# Triac.net
KiCad netlist of a schematic drawn in EAGLE
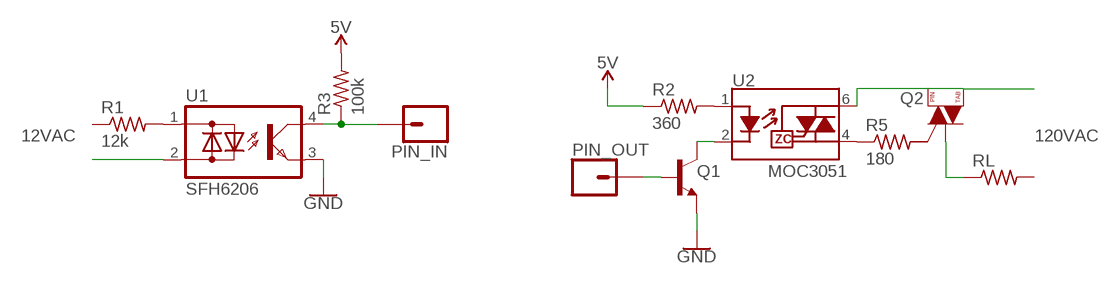
[diagram p0: schematic, sheet 1]

(export (version "E")
  (design (tool "Eeschema 10.0.6"))
  (components
    (comp (ref "PIN_IN")
      (value "CONN_01")
      (footprint "eagle-import:1X01")
      (libsource (lib "eagle-import") (part "CONN_01"))
    )
    (comp (ref "PIN_OUT")
      (value "CONN_01")
      (footprint "eagle-import:1X01")
      (libsource (lib "eagle-import") (part "CONN_01"))
    )
    (comp (ref "Q1")
      (value "TRANS_NPN-MMBTA42")
      (footprint "eagle-import:SOT23-3")
      (libsource (lib "eagle-import") (part "TRANS_NPN-MMBTA42"))
    )
    (comp (ref "Q2")
      (value "BT137-600E")
      (footprint "eagle-import:SOT223")
      (libsource (lib "eagle-import") (part "TRIAC-Z0103MN"))
    )
    (comp (ref "R1")
      (value "12k")
      (footprint "eagle-import:R0603")
      (libsource (lib "eagle-import") (part "R-US_R0603"))
    )
    (comp (ref "R2")
      (value "360")
      (footprint "eagle-import:R0603")
      (libsource (lib "eagle-import") (part "R-US_R0603"))
    )
    (comp (ref "R3")
      (value "100k")
      (footprint "eagle-import:R0603")
      (libsource (lib "eagle-import") (part "R-US_R0603"))
    )
    (comp (ref "R5")
      (value "180")
      (footprint "eagle-import:R0603")
      (libsource (lib "eagle-import") (part "R-US_R0603"))
    )
    (comp (ref "RL")
      (value "R-US_R0603")
      (footprint "eagle-import:R0603")
      (libsource (lib "eagle-import") (part "R-US_R0603"))
    )
    (comp (ref "U1")
      (value "SFH6206")
      (footprint "eagle-import:DIL4-SMD")
      (fields (field (name "MF") "VISHAY/TELEFUNKEN") (field (name "MPN") "SFH6206-3"))
      (libsource (lib "eagle-import") (part "SFH6206"))
    )
    (comp (ref "U2")
      (value "TRIAC_OPTOCOUPLER-MOC3063SM")
      (footprint "eagle-import:DIP8SMD")
      (libsource (lib "eagle-import") (part "TRIAC_OPTOCOUPLER-MOC3063SM"))
    )
  )
  (nets
    (net (code "1") (name "5V") (class "Default")
      (node (ref "R2") (pin "1") (pinfunction "1_1") (pintype "passive"))
      (node (ref "R3") (pin "2") (pinfunction "2_2") (pintype "passive"))
    )
    (net (code "2") (name "GND") (class "Default")
      (node (ref "Q1") (pin "2") (pinfunction "E_2") (pintype "passive"))
      (node (ref "U1") (pin "3") (pinfunction "E_3") (pintype "passive"))
    )
    (net (code "3") (name "Net-(Q1-B)") (class "Default")
      (node (ref "PIN_OUT") (pin "1") (pinfunction "1_1") (pintype "passive"))
      (node (ref "Q1") (pin "1") (pinfunction "B_1") (pintype "passive"))
    )
    (net (code "4") (name "Net-(Q1-C)") (class "Default")
      (node (ref "Q1") (pin "3") (pinfunction "C_3") (pintype "passive"))
      (node (ref "U2") (pin "2") (pinfunction "K_2") (pintype "bidirectional"))
    )
    (net (code "5") (name "Net-(Q2-T1)") (class "Default")
      (node (ref "Q2") (pin "1") (pinfunction "T1_1") (pintype "bidirectional"))
      (node (ref "RL") (pin "1") (pinfunction "1_1") (pintype "passive"))
    )
    (net (code "6") (name "Net-(U1-AC1)") (class "Default")
      (node (ref "R1") (pin "2") (pinfunction "2_2") (pintype "passive"))
      (node (ref "U1") (pin "1") (pinfunction "AC1_1") (pintype "passive"))
    )
    (net (code "7") (name "Net-(U1-C)") (class "Default")
      (node (ref "PIN_IN") (pin "1") (pinfunction "1_1") (pintype "passive"))
      (node (ref "R3") (pin "1") (pinfunction "1_1") (pintype "passive"))
      (node (ref "U1") (pin "4") (pinfunction "C_4") (pintype "passive"))
    )
    (net (code "8") (name "Net-(U2-A)") (class "Default")
      (node (ref "R2") (pin "2") (pinfunction "2_2") (pintype "passive"))
      (node (ref "U2") (pin "1") (pinfunction "A_1") (pintype "bidirectional"))
    )
    (net (code "9") (name "Net-(U2-T1)") (class "Default")
      (node (ref "Q2") (pin "2") (pinfunction "T2_2") (pintype "passive"))
      (node (ref "Q2") (pin "4") (pinfunction "T2_4") (pintype "passive"))
      (node (ref "U2") (pin "6") (pinfunction "T1_6") (pintype "bidirectional"))
    )
    (net (code "10") (name "Net-(U2-T2)") (class "Default")
      (node (ref "R5") (pin "1") (pinfunction "1_1") (pintype "passive"))
      (node (ref "U2") (pin "4") (pinfunction "T2_4") (pintype "bidirectional"))
    )
    (net (code "11") (name "unconnected-(Q2-G-Pad3)") (class "Default")
      (node (ref "Q2") (pin "3") (pinfunction "G_3") (pintype "bidirectional"))
    )
    (net (code "12") (name "unconnected-(R1-Pad1)") (class "Default")
      (node (ref "R1") (pin "1") (pinfunction "1_1") (pintype "passive"))
    )
    (net (code "13") (name "unconnected-(R5-Pad2)") (class "Default")
      (node (ref "R5") (pin "2") (pinfunction "2_2") (pintype "passive"))
    )
    (net (code "14") (name "unconnected-(RL-Pad2)") (class "Default")
      (node (ref "RL") (pin "2") (pinfunction "2_2") (pintype "passive"))
    )
    (net (code "15") (name "unconnected-(U1-AC2-Pad2)") (class "Default")
      (node (ref "U1") (pin "2") (pinfunction "AC2_2") (pintype "passive"))
    )
  )
)
